# MetaSenseV02_3.net
KiCad netlist of a schematic drawn in EAGLE
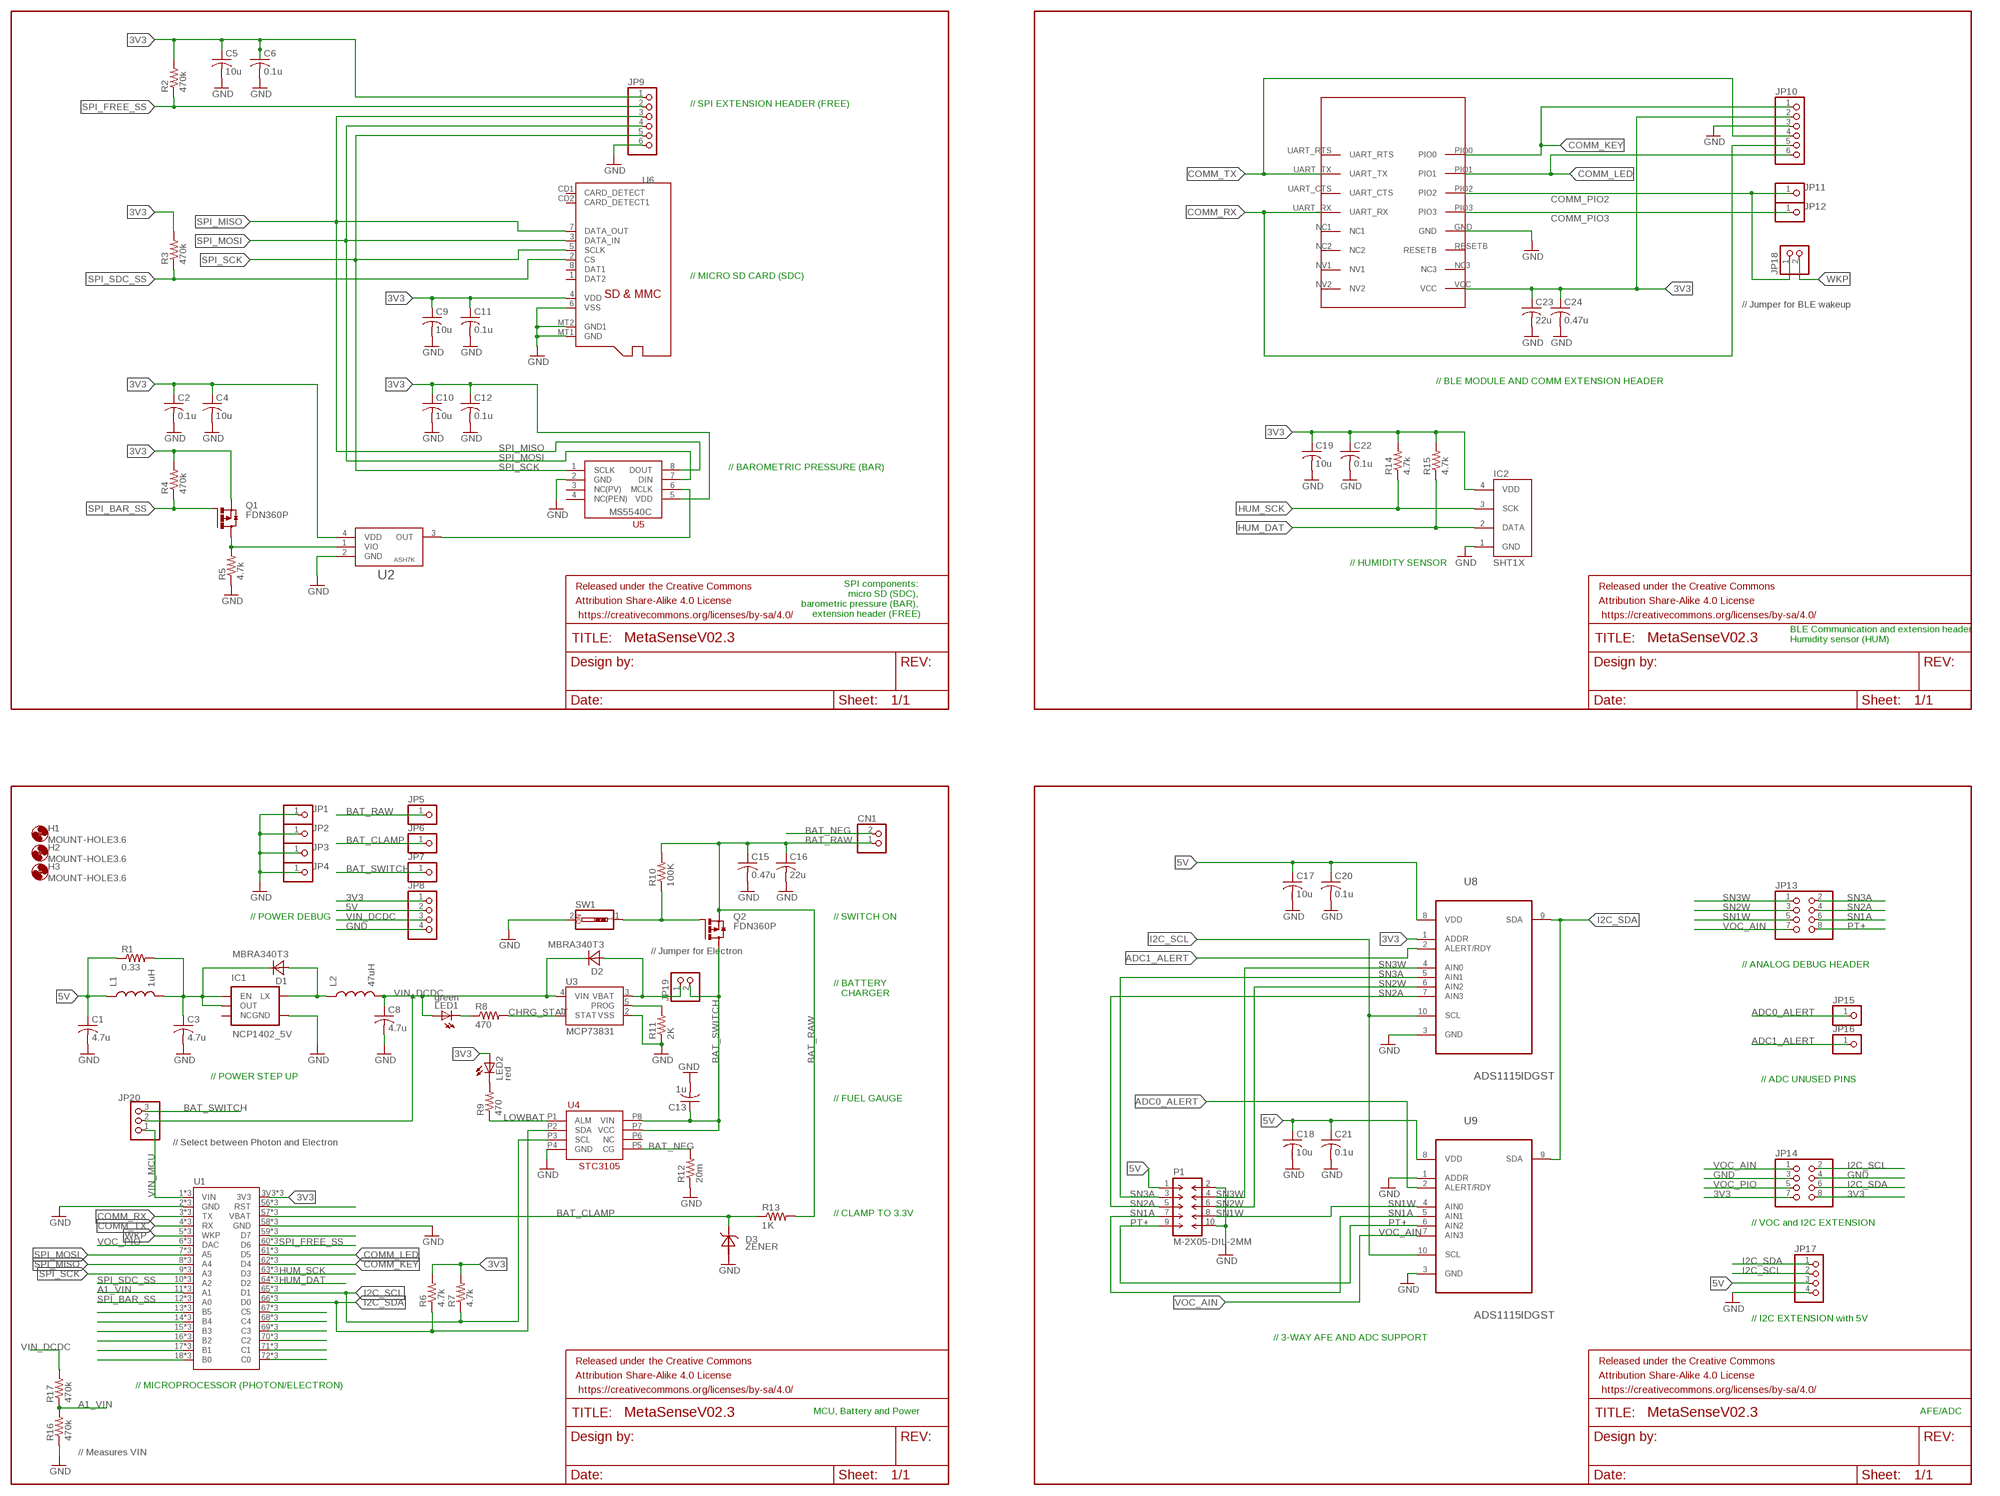
[diagram p0: schematic, sheet 1]

(export (version "E")
  (design (tool "Eeschema 10.0.6"))
  (components
    (comp (ref "C1")
      (value "4.7u")
      (footprint "eagle-import:C0805")
      (fields (field (name "MF") "VISHAY/DALE") (field (name "MPN") "IHLP2525CZER4R7M01"))
      (libsource (lib "eagle-import") (part "C-USC0805"))
    )
    (comp (ref "C2")
      (value "0.1u")
      (footprint "eagle-import:C0805")
      (fields (field (name "MF") "KEMET") (field (name "MPN") "C0603C102J5GACTU"))
      (libsource (lib "eagle-import") (part "C-USC0805"))
    )
    (comp (ref "C3")
      (value "4.7u")
      (footprint "eagle-import:C0805")
      (fields (field (name "MF") "VISHAY/DALE") (field (name "MPN") "IHLP2525CZER4R7M01"))
      (libsource (lib "eagle-import") (part "C-USC0805"))
    )
    (comp (ref "C4")
      (value "10u")
      (footprint "eagle-import:C0805")
      (fields (field (name "MPN") "C0805C106Z8VACTU"))
      (libsource (lib "eagle-import") (part "C-USC0805"))
    )
    (comp (ref "C5")
      (value "10u")
      (footprint "eagle-import:C0805")
      (fields (field (name "MPN") "C0805C106Z8VACTU"))
      (libsource (lib "eagle-import") (part "C-USC0805"))
    )
    (comp (ref "C6")
      (value "0.1u")
      (footprint "eagle-import:C0805")
      (fields (field (name "MF") "KEMET") (field (name "MPN") "C0603C102J5GACTU"))
      (libsource (lib "eagle-import") (part "C-USC0805"))
    )
    (comp (ref "C8")
      (value "4.7u")
      (footprint "eagle-import:C0805")
      (fields (field (name "MF") "VISHAY/DALE") (field (name "MPN") "IHLP2525CZER4R7M01"))
      (libsource (lib "eagle-import") (part "C-USC0805"))
    )
    (comp (ref "C9")
      (value "10u")
      (footprint "eagle-import:C0805")
      (fields (field (name "MPN") "C0805C106Z8VACTU"))
      (libsource (lib "eagle-import") (part "C-USC0805"))
    )
    (comp (ref "C10")
      (value "10u")
      (footprint "eagle-import:C0805")
      (fields (field (name "MPN") "C0805C106Z8VACTU"))
      (libsource (lib "eagle-import") (part "C-USC0805"))
    )
    (comp (ref "C11")
      (value "0.1u")
      (footprint "eagle-import:C0805")
      (fields (field (name "MF") "KEMET") (field (name "MPN") "C0603C102J5GACTU"))
      (libsource (lib "eagle-import") (part "C-USC0805"))
    )
    (comp (ref "C12")
      (value "0.1u")
      (footprint "eagle-import:C0805")
      (fields (field (name "MF") "KEMET") (field (name "MPN") "C0603C102J5GACTU"))
      (libsource (lib "eagle-import") (part "C-USC0805"))
    )
    (comp (ref "C13")
      (value "1u")
      (footprint "eagle-import:C0805")
      (fields (field (name "MF") "KEMET") (field (name "MPN") "C0402C471K5RACTU"))
      (libsource (lib "eagle-import") (part "C-USC0805"))
    )
    (comp (ref "C15")
      (value "0.47u")
      (footprint "eagle-import:C0805")
      (fields (field (name "MF") "KEMET") (field (name "MPN") "C0402C471K5RACTU"))
      (libsource (lib "eagle-import") (part "C-USC0805"))
    )
    (comp (ref "C16")
      (value "22u")
      (footprint "eagle-import:C0805")
      (libsource (lib "eagle-import") (part "C-USC0805"))
    )
    (comp (ref "C17")
      (value "10u")
      (footprint "eagle-import:C0805")
      (fields (field (name "MPN") "C0805C106Z8VACTU"))
      (libsource (lib "eagle-import") (part "C-USC0805"))
    )
    (comp (ref "C18")
      (value "10u")
      (footprint "eagle-import:C0805")
      (fields (field (name "MPN") "C0805C106Z8VACTU"))
      (libsource (lib "eagle-import") (part "C-USC0805"))
    )
    (comp (ref "C19")
      (value "10u")
      (footprint "eagle-import:C0805")
      (fields (field (name "MPN") "C0805C106Z8VACTU"))
      (libsource (lib "eagle-import") (part "C-USC0805"))
    )
    (comp (ref "C20")
      (value "0.1u")
      (footprint "eagle-import:C0805")
      (fields (field (name "MF") "KEMET") (field (name "MPN") "C0603C102J5GACTU"))
      (libsource (lib "eagle-import") (part "C-USC0805"))
    )
    (comp (ref "C21")
      (value "0.1u")
      (footprint "eagle-import:C0805")
      (fields (field (name "MF") "KEMET") (field (name "MPN") "C0603C102J5GACTU"))
      (libsource (lib "eagle-import") (part "C-USC0805"))
    )
    (comp (ref "C22")
      (value "0.1u")
      (footprint "eagle-import:C0805")
      (fields (field (name "MF") "KEMET") (field (name "MPN") "C0603C102J5GACTU"))
      (libsource (lib "eagle-import") (part "C-USC0805"))
    )
    (comp (ref "C23")
      (value "22u")
      (footprint "eagle-import:C0805")
      (libsource (lib "eagle-import") (part "C-USC0805"))
    )
    (comp (ref "C24")
      (value "0.47u")
      (footprint "eagle-import:C0805")
      (fields (field (name "MF") "KEMET") (field (name "MPN") "C0402C471K5RACTU"))
      (libsource (lib "eagle-import") (part "C-USC0805"))
    )
    (comp (ref "CN1")
      (value "JST_2PIN-THM")
      (footprint "eagle-import:JST-PH-2-THM")
      (libsource (lib "eagle-import") (part "JST_2PIN-THM"))
    )
    (comp (ref "D1")
      (value "MBRA340T3")
      (footprint "eagle-import:SMA")
      (libsource (lib "eagle-import") (part "MBRA340T3"))
    )
    (comp (ref "D2")
      (value "MBRA340T3")
      (footprint "eagle-import:SMA")
      (libsource (lib "eagle-import") (part "MBRA340T3"))
    )
    (comp (ref "D3")
      (value "ZENER")
      (footprint "eagle-import:SOD-123_MINI-SMA")
      (libsource (lib "eagle-import") (part "ZENER"))
    )
    (comp (ref "FRAME1")
      (value "FRAME-LETTERNO_PACKAGE")
      (footprint "eagle-import:DUMMY")
      (fields
        (field (name "DESIGNER") "Christine Chan")
        (field (name "VERSION") "v02")
        (field (name "OC_NEWARK") "unknown")
      )
      (libsource (lib "eagle-import") (part "FRAME-LETTERNO_PACKAGE"))
    )
    (comp (ref "FRAME2")
      (value "FRAME-LETTERNO_PACKAGE")
      (footprint "eagle-import:DUMMY")
      (fields
        (field (name "DESIGNER") "Christine Chan")
        (field (name "OC_NEWARK") "unknown")
        (field (name "VERSION") "v02")
      )
      (libsource (lib "eagle-import") (part "FRAME-LETTERNO_PACKAGE"))
    )
    (comp (ref "FRAME3")
      (value "FRAME-LETTERNO_PACKAGE")
      (footprint "eagle-import:DUMMY")
      (fields
        (field (name "DESIGNER") "Christine Chan")
        (field (name "OC_NEWARK") "unknown")
        (field (name "VERSION") "v02")
      )
      (libsource (lib "eagle-import") (part "FRAME-LETTERNO_PACKAGE"))
    )
    (comp (ref "FRAME4")
      (value "FRAME-LETTERNO_PACKAGE")
      (footprint "eagle-import:DUMMY")
      (fields
        (field (name "DESIGNER") "Christine Chan")
        (field (name "VERSION") "v02")
        (field (name "OC_NEWARK") "unknown")
      )
      (libsource (lib "eagle-import") (part "FRAME-LETTERNO_PACKAGE"))
    )
    (comp (ref "H1")
      (value "MOUNT-HOLE3.6")
      (footprint "eagle-import:3,6")
      (libsource (lib "eagle-import") (part "MOUNT-HOLE3.6"))
    )
    (comp (ref "H2")
      (value "MOUNT-HOLE3.6")
      (footprint "eagle-import:3,6")
      (libsource (lib "eagle-import") (part "MOUNT-HOLE3.6"))
    )
    (comp (ref "H3")
      (value "MOUNT-HOLE3.6")
      (footprint "eagle-import:3,6")
      (libsource (lib "eagle-import") (part "MOUNT-HOLE3.6"))
    )
    (comp (ref "IC1")
      (value "NCP1402_5V")
      (footprint "eagle-import:SOT23-5")
      (fields (field (name "MF") "ON SEMICONDUCTOR") (field (name "MPN") "NCP1402SN50T1G"))
      (libsource (lib "eagle-import") (part "V_REG_NCP1400_5V"))
    )
    (comp (ref "IC2")
      (value "SHT1X")
      (footprint "eagle-import:SHT1X")
      (fields (field (name "MF") "SENSIRION AG") (field (name "MPN") "SHT11"))
      (libsource (lib "eagle-import") (part "SHT1X"))
    )
    (comp (ref "JP1")
      (value "PINHD-1X1")
      (footprint "eagle-import:1X01")
      (libsource (lib "eagle-import") (part "pinhead_PINHD-1X1"))
    )
    (comp (ref "JP2")
      (value "PINHD-1X1")
      (footprint "eagle-import:1X01")
      (libsource (lib "eagle-import") (part "pinhead_PINHD-1X1"))
    )
    (comp (ref "JP3")
      (value "PINHD-1X1")
      (footprint "eagle-import:1X01")
      (libsource (lib "eagle-import") (part "pinhead_PINHD-1X1"))
    )
    (comp (ref "JP4")
      (value "PINHD-1X1")
      (footprint "eagle-import:1X01")
      (libsource (lib "eagle-import") (part "pinhead_PINHD-1X1"))
    )
    (comp (ref "JP5")
      (value "PINHD-1X1")
      (footprint "eagle-import:1X01")
      (libsource (lib "eagle-import") (part "pinhead_PINHD-1X1"))
    )
    (comp (ref "JP6")
      (value "PINHD-1X1")
      (footprint "eagle-import:1X01")
      (libsource (lib "eagle-import") (part "pinhead_PINHD-1X1"))
    )
    (comp (ref "JP7")
      (value "PINHD-1X1")
      (footprint "eagle-import:1X01")
      (libsource (lib "eagle-import") (part "pinhead_PINHD-1X1"))
    )
    (comp (ref "JP8")
      (value "PINHD-1X4")
      (footprint "eagle-import:1X04")
      (libsource (lib "eagle-import") (part "PINHD-1X4"))
    )
    (comp (ref "JP9")
      (value "PINHD-1X6")
      (footprint "eagle-import:1X06")
      (libsource (lib "eagle-import") (part "PINHD-1X6"))
    )
    (comp (ref "JP10")
      (value "PINHD-1X6")
      (footprint "eagle-import:1X06")
      (libsource (lib "eagle-import") (part "PINHD-1X6"))
    )
    (comp (ref "JP11")
      (value "PINHD-1X1")
      (footprint "eagle-import:1X01")
      (libsource (lib "eagle-import") (part "pinhead_PINHD-1X1"))
    )
    (comp (ref "JP12")
      (value "PINHD-1X1")
      (footprint "eagle-import:1X01")
      (libsource (lib "eagle-import") (part "pinhead_PINHD-1X1"))
    )
    (comp (ref "JP13")
      (value "PINHD-2X4")
      (footprint "eagle-import:2X04")
      (libsource (lib "eagle-import") (part "PINHD-2X4"))
    )
    (comp (ref "JP14")
      (value "PINHD-2X4")
      (footprint "eagle-import:2X04")
      (libsource (lib "eagle-import") (part "PINHD-2X4"))
    )
    (comp (ref "JP15")
      (value "PINHD-1X1")
      (footprint "eagle-import:1X01")
      (libsource (lib "eagle-import") (part "PINHD-1X1"))
    )
    (comp (ref "JP16")
      (value "PINHD-1X1")
      (footprint "eagle-import:1X01")
      (libsource (lib "eagle-import") (part "PINHD-1X1"))
    )
    (comp (ref "JP17")
      (value "PINHD-1X4")
      (footprint "eagle-import:1X04")
      (libsource (lib "eagle-import") (part "PINHD-1X4"))
    )
    (comp (ref "JP18")
      (value "PINHD-1X2")
      (footprint "eagle-import:1X02")
      (libsource (lib "eagle-import") (part "PINHD-1X2"))
    )
    (comp (ref "JP19")
      (value "PINHD-1X2")
      (footprint "eagle-import:1X02")
      (libsource (lib "eagle-import") (part "PINHD-1X2"))
    )
    (comp (ref "JP20")
      (value "PINHD-1X3")
      (footprint "eagle-import:1X03")
      (libsource (lib "eagle-import") (part "PINHD-1X3"))
    )
    (comp (ref "L1")
      (value "1uH")
      (footprint "eagle-import:0805")
      (fields (field (name "MPN") "LQM21NN1R0K10D"))
      (libsource (lib "eagle-import") (part "INDUCTOR0805"))
    )
    (comp (ref "L2")
      (value "47uH")
      (footprint "eagle-import:0805")
      (libsource (lib "eagle-import") (part "INDUCTOR0805"))
    )
    (comp (ref "LED1")
      (value "green")
      (footprint "eagle-import:CHIPLED_0805")
      (fields (field (name "MPN") "NTE30003"))
      (libsource (lib "eagle-import") (part "LEDCHIPLED_0805"))
    )
    (comp (ref "LED2")
      (value "red")
      (footprint "eagle-import:CHIPLED_0805")
      (fields (field (name "MPN") "NTE30002"))
      (libsource (lib "eagle-import") (part "LEDCHIPLED_0805"))
    )
    (comp (ref "P1")
      (value "M-2X05-DIL-2MM")
      (footprint "eagle-import:DIL-2MM-2X05")
      (libsource (lib "eagle-import") (part "M-2X05-DIL-2MM"))
    )
    (comp (ref "Q1")
      (value "FDN360P")
      (footprint "eagle-import:SUPER-SOT3")
      (fields (field (name "MF") "FAIRCHILD SEMICONDUCTOR"))
      (libsource (lib "eagle-import") (part "FDN360P"))
    )
    (comp (ref "Q2")
      (value "FDN360P")
      (footprint "eagle-import:SUPER-SOT3")
      (fields (field (name "MF") "FAIRCHILD SEMICONDUCTOR"))
      (libsource (lib "eagle-import") (part "FDN360P"))
    )
    (comp (ref "R1")
      (value "0.33")
      (footprint "eagle-import:R0805")
      (libsource (lib "eagle-import") (part "R-US_R0805"))
    )
    (comp (ref "R2")
      (value "470k")
      (footprint "eagle-import:R0805")
      (fields (field (name "MF") "VISHAY/DALE") (field (name "MPN") "CRCW0805470KJNEA"))
      (libsource (lib "eagle-import") (part "R-US_R0805"))
    )
    (comp (ref "R3")
      (value "470k")
      (footprint "eagle-import:R0805")
      (fields (field (name "MF") "VISHAY/DALE") (field (name "MPN") "CRCW0805470KJNEA"))
      (libsource (lib "eagle-import") (part "R-US_R0805"))
    )
    (comp (ref "R4")
      (value "470k")
      (footprint "eagle-import:R0805")
      (fields (field (name "MF") "VISHAY/DALE") (field (name "MPN") "CRCW0805470KJNEA"))
      (libsource (lib "eagle-import") (part "R-US_R0805"))
    )
    (comp (ref "R5")
      (value "4.7k")
      (footprint "eagle-import:R0805")
      (fields (field (name "MF") "VISHAY/DALE") (field (name "MPN") "CRCW08054K70JNEA"))
      (libsource (lib "eagle-import") (part "R-US_R0805"))
    )
    (comp (ref "R6")
      (value "4.7k")
      (footprint "eagle-import:R0805")
      (fields (field (name "MF") "VISHAY/DALE") (field (name "MPN") "CRCW08054K70JNEA"))
      (libsource (lib "eagle-import") (part "R-US_R0805"))
    )
    (comp (ref "R7")
      (value "4.7k")
      (footprint "eagle-import:R0805")
      (fields (field (name "MF") "VISHAY/DALE") (field (name "MPN") "CRCW08054K70JNEA"))
      (libsource (lib "eagle-import") (part "R-US_R0805"))
    )
    (comp (ref "R8")
      (value "470")
      (footprint "eagle-import:R0805")
      (libsource (lib "eagle-import") (part "R-US_R0805"))
    )
    (comp (ref "R9")
      (value "470")
      (footprint "eagle-import:R0805")
      (libsource (lib "eagle-import") (part "R-US_R0805"))
    )
    (comp (ref "R10")
      (value "100K")
      (footprint "eagle-import:R0805")
      (fields (field (name "MPN") "ERA-6AEB104V"))
      (libsource (lib "eagle-import") (part "R-US_R0805"))
    )
    (comp (ref "R11")
      (value "2K")
      (footprint "eagle-import:R0805")
      (libsource (lib "eagle-import") (part "R-US_R0805"))
    )
    (comp (ref "R12")
      (value "20m")
      (footprint "eagle-import:R0805")
      (libsource (lib "eagle-import") (part "R-US_R0805"))
    )
    (comp (ref "R13")
      (value "1K")
      (footprint "eagle-import:R0805")
      (fields (field (name "MPN") "ERJ-6ENF1001V"))
      (libsource (lib "eagle-import") (part "R-US_R0805"))
    )
    (comp (ref "R14")
      (value "4.7k")
      (footprint "eagle-import:R0805")
      (fields (field (name "MF") "VISHAY/DALE") (field (name "MPN") "CRCW08054K70JNEA"))
      (libsource (lib "eagle-import") (part "R-US_R0805"))
    )
    (comp (ref "R15")
      (value "4.7k")
      (footprint "eagle-import:R0805")
      (fields (field (name "MF") "VISHAY/DALE") (field (name "MPN") "CRCW08054K70JNEA"))
      (libsource (lib "eagle-import") (part "R-US_R0805"))
    )
    (comp (ref "R16")
      (value "470k")
      (footprint "eagle-import:R0805")
      (fields (field (name "MF") "VISHAY/DALE") (field (name "MPN") "CRCW08054K70JNEA"))
      (libsource (lib "eagle-import") (part "R-US_R0805"))
    )
    (comp (ref "R17")
      (value "470k")
      (footprint "eagle-import:R0805")
      (fields (field (name "MF") "VISHAY/DALE") (field (name "MPN") "CRCW08054K70JNEA"))
      (libsource (lib "eagle-import") (part "R-US_R0805"))
    )
    (comp (ref "SW1")
      (value "SW_DIP-1")
      (footprint "eagle-import:EDG-01")
      (libsource (lib "eagle-import") (part "SW_DIP-1"))
    )
    (comp (ref "U1")
      (value "ELECTRONDUALROW")
      (footprint "eagle-import:ELECTRON_DUAL-ROW")
      (libsource (lib "eagle-import") (part "ELECTRONDUALROW"))
    )
    (comp (ref "U2")
      (value "ASH7K-OSCILLATOR")
      (footprint "eagle-import:SMD-4PAD")
      (libsource (lib "eagle-import") (part "ASH7K-OSCILLATOR"))
    )
    (comp (ref "U3")
      (value "MCP73831")
      (footprint "eagle-import:SOT23-5")
      (fields (field (name "MPN") "MCP73831T-2DCI/OT"))
      (libsource (lib "eagle-import") (part "MCP73831"))
    )
    (comp (ref "U4")
      (value "STC3105")
      (footprint "eagle-import:TDFN-8-3X2MM")
      (libsource (lib "eagle-import") (part "STC3105"))
    )
    (comp (ref "U5")
      (value "MS5540CSMD")
      (footprint "eagle-import:SMD-HYBRID")
      (libsource (lib "eagle-import") (part "MS5540CSMD"))
    )
    (comp (ref "U6")
      (value "MICROSD")
      (footprint "eagle-import:MICROSD")
      (fields (field (name "MPN") "2908-05WB-MG"))
      (libsource (lib "eagle-import") (part "MICROSD"))
    )
    (comp (ref "U7")
      (value "HM-11")
      (footprint "eagle-import:HM-11")
      (libsource (lib "eagle-import") (part "HM-11"))
    )
    (comp (ref "U8")
      (value "ADS1115IDGST")
      (footprint "eagle-import:SOP50P490X110-10N")
      (libsource (lib "eagle-import") (part "ADS1115IDGST"))
    )
    (comp (ref "U9")
      (value "ADS1115IDGST")
      (footprint "eagle-import:SOP50P490X110-10N")
      (libsource (lib "eagle-import") (part "ADS1115IDGST"))
    )
  )
  (nets
    (net (code "1") (name "/A1_VIN") (class "Default")
      (node (ref "R16") (pin "2") (pinfunction "2_2") (pintype "passive"))
      (node (ref "R17") (pin "1") (pinfunction "1_1") (pintype "passive"))
      (node (ref "U1") (pin "11") (pinfunction "A1_11") (pintype "bidirectional"))
      (node (ref "U1") (pin "47") (pinfunction "A1_47") (pintype "bidirectional"))
      (node (ref "U1") (pin "A1") (pinfunction "A1_A1") (pintype "bidirectional"))
    )
    (net (code "2") (name "/BAT_CLAMP") (class "Default")
      (node (ref "D3") (pin "C") (pinfunction "CAT_C") (pintype "bidirectional"))
      (node (ref "JP6") (pin "1") (pinfunction "1_1") (pintype "passive"))
      (node (ref "R13") (pin "1") (pinfunction "1_1") (pintype "passive"))
      (node (ref "U1") (pin "57") (pinfunction "VBAT_57") (pintype "passive"))
      (node (ref "U1") (pin "93") (pinfunction "VBAT_93") (pintype "passive"))
      (node (ref "U1") (pin "VBAT") (pinfunction "VBAT_VBAT") (pintype "passive"))
    )
    (net (code "3") (name "/BAT_NEG") (class "Default")
      (node (ref "CN1") (pin "2") (pinfunction "1_2") (pintype "passive"))
      (node (ref "R12") (pin "2") (pinfunction "2_2") (pintype "passive"))
      (node (ref "U4") (pin "P5") (pinfunction "CG_P5") (pintype "bidirectional"))
    )
    (net (code "4") (name "/BAT_RAW") (class "Default")
      (node (ref "C15") (pin "1") (pinfunction "1_1") (pintype "passive"))
      (node (ref "C16") (pin "1") (pinfunction "1_1") (pintype "passive"))
      (node (ref "CN1") (pin "1") (pinfunction "2_1") (pintype "passive"))
      (node (ref "JP5") (pin "1") (pinfunction "1_1") (pintype "passive"))
      (node (ref "Q2") (pin "2") (pinfunction "S_2") (pintype "passive"))
      (node (ref "R10") (pin "2") (pinfunction "2_2") (pintype "passive"))
      (node (ref "R13") (pin "2") (pinfunction "2_2") (pintype "passive"))
    )
    (net (code "5") (name "/BAT_SWITCH") (class "Default")
      (node (ref "C13") (pin "1") (pinfunction "1_1") (pintype "passive"))
      (node (ref "JP19") (pin "2") (pinfunction "2_2") (pintype "passive"))
      (node (ref "JP20") (pin "3") (pinfunction "3_3") (pintype "passive"))
      (node (ref "JP7") (pin "1") (pinfunction "1_1") (pintype "passive"))
      (node (ref "Q2") (pin "3") (pinfunction "D_3") (pintype "passive"))
      (node (ref "U4") (pin "P7") (pinfunction "VCC_P7") (pintype "bidirectional"))
      (node (ref "U4") (pin "P8") (pinfunction "VIN_P8") (pintype "bidirectional"))
    )
    (net (code "6") (name "/CHRG_STAT") (class "Default")
      (node (ref "R8") (pin "2") (pinfunction "2_2") (pintype "passive"))
      (node (ref "U3") (pin "1") (pinfunction "STAT_1") (pintype "output"))
    )
    (net (code "7") (name "/COMM_PIO2") (class "Default")
      (node (ref "JP11") (pin "1") (pinfunction "1_1") (pintype "passive"))
      (node (ref "JP18") (pin "1") (pinfunction "1_1") (pintype "passive"))
      (node (ref "U7") (pin "PIO2") (pinfunction "PIO2_PIO2") (pintype "bidirectional"))
    )
    (net (code "8") (name "/COMM_PIO3") (class "Default")
      (node (ref "JP12") (pin "1") (pinfunction "1_1") (pintype "passive"))
      (node (ref "U7") (pin "PIO3") (pinfunction "PIO3_PIO3") (pintype "bidirectional"))
    )
    (net (code "9") (name "/LOWBAT") (class "Default")
      (node (ref "R9") (pin "1") (pinfunction "1_1") (pintype "passive"))
      (node (ref "U4") (pin "P1") (pinfunction "ALM_P1") (pintype "bidirectional"))
    )
    (net (code "10") (name "/PT+") (class "Default")
      (node (ref "JP13") (pin "8") (pinfunction "8_8") (pintype "passive"))
      (node (ref "P1") (pin "9") (pinfunction "9_9") (pintype "passive"))
      (node (ref "U9") (pin "6") (pinfunction "AIN2_6") (pintype "input"))
    )
    (net (code "11") (name "/SN1A") (class "Default")
      (node (ref "JP13") (pin "6") (pinfunction "6_6") (pintype "passive"))
      (node (ref "P1") (pin "7") (pinfunction "7_7") (pintype "passive"))
      (node (ref "U9") (pin "5") (pinfunction "AIN1_5") (pintype "input"))
    )
    (net (code "12") (name "/SN1W") (class "Default")
      (node (ref "JP13") (pin "5") (pinfunction "5_5") (pintype "passive"))
      (node (ref "P1") (pin "8") (pinfunction "8_8") (pintype "passive"))
      (node (ref "U9") (pin "4") (pinfunction "AIN0_4") (pintype "input"))
    )
    (net (code "13") (name "/SN2A") (class "Default")
      (node (ref "JP13") (pin "4") (pinfunction "4_4") (pintype "passive"))
      (node (ref "P1") (pin "5") (pinfunction "5_5") (pintype "passive"))
      (node (ref "U8") (pin "7") (pinfunction "AIN3_7") (pintype "input"))
    )
    (net (code "14") (name "/SN2W") (class "Default")
      (node (ref "JP13") (pin "3") (pinfunction "3_3") (pintype "passive"))
      (node (ref "P1") (pin "6") (pinfunction "6_6") (pintype "passive"))
      (node (ref "U8") (pin "6") (pinfunction "AIN2_6") (pintype "input"))
    )
    (net (code "15") (name "/SN3A") (class "Default")
      (node (ref "JP13") (pin "2") (pinfunction "2_2") (pintype "passive"))
      (node (ref "P1") (pin "3") (pinfunction "3_3") (pintype "passive"))
      (node (ref "U8") (pin "5") (pinfunction "AIN1_5") (pintype "input"))
    )
    (net (code "16") (name "/SN3W") (class "Default")
      (node (ref "JP13") (pin "1") (pinfunction "1_1") (pintype "passive"))
      (node (ref "P1") (pin "4") (pinfunction "4_4") (pintype "passive"))
      (node (ref "U8") (pin "4") (pinfunction "AIN0_4") (pintype "input"))
    )
    (net (code "17") (name "/VIN_DCDC") (class "Default")
      (node (ref "C8") (pin "1") (pinfunction "1_1") (pintype "passive"))
      (node (ref "D2") (pin "C") (pinfunction "C_C") (pintype "passive"))
      (node (ref "JP20") (pin "2") (pinfunction "2_2") (pintype "passive"))
      (node (ref "JP8") (pin "3") (pinfunction "3_3") (pintype "passive"))
      (node (ref "L2") (pin "2") (pinfunction "2_2") (pintype "passive"))
      (node (ref "LED1") (pin "A") (pinfunction "A_A") (pintype "passive"))
      (node (ref "R17") (pin "2") (pinfunction "2_2") (pintype "passive"))
      (node (ref "U3") (pin "4") (pinfunction "VIN_4") (pintype "power_in"))
    )
    (net (code "18") (name "/VIN_MCU") (class "Default")
      (node (ref "JP20") (pin "1") (pinfunction "1_1") (pintype "passive"))
      (node (ref "U1") (pin "1") (pinfunction "VIN_1") (pintype "power_in"))
      (node (ref "U1") (pin "37") (pinfunction "VIN_37") (pintype "power_in"))
      (node (ref "U1") (pin "VIN") (pinfunction "VIN_VIN") (pintype "power_in"))
    )
    (net (code "19") (name "/VOC_PIO") (class "Default")
      (node (ref "JP14") (pin "5") (pinfunction "5_5") (pintype "passive"))
      (node (ref "U1") (pin "42") (pinfunction "DAC_42") (pintype "bidirectional"))
      (node (ref "U1") (pin "6") (pinfunction "DAC_6") (pintype "bidirectional"))
      (node (ref "U1") (pin "DAC") (pinfunction "DAC_DAC") (pintype "bidirectional"))
    )
    (net (code "20") (name "3V3") (class "Default")
      (node (ref "C10") (pin "1") (pinfunction "1_1") (pintype "passive"))
      (node (ref "C11") (pin "1") (pinfunction "1_1") (pintype "passive"))
      (node (ref "C12") (pin "1") (pinfunction "1_1") (pintype "passive"))
      (node (ref "C19") (pin "1") (pinfunction "1_1") (pintype "passive"))
      (node (ref "C2") (pin "1") (pinfunction "1_1") (pintype "passive"))
      (node (ref "C22") (pin "1") (pinfunction "1_1") (pintype "passive"))
      (node (ref "C23") (pin "1") (pinfunction "1_1") (pintype "passive"))
      (node (ref "C24") (pin "1") (pinfunction "1_1") (pintype "passive"))
      (node (ref "C4") (pin "1") (pinfunction "1_1") (pintype "passive"))
      (node (ref "C5") (pin "1") (pinfunction "1_1") (pintype "passive"))
      (node (ref "C6") (pin "1") (pinfunction "1_1") (pintype "passive"))
      (node (ref "C9") (pin "1") (pinfunction "1_1") (pintype "passive"))
      (node (ref "IC2") (pin "4") (pinfunction "VDD_4") (pintype "power_in"))
      (node (ref "JP10") (pin "2") (pinfunction "2_2") (pintype "passive"))
      (node (ref "JP14") (pin "7") (pinfunction "7_7") (pintype "passive"))
      (node (ref "JP14") (pin "8") (pinfunction "8_8") (pintype "passive"))
      (node (ref "JP8") (pin "1") (pinfunction "1_1") (pintype "passive"))
      (node (ref "JP9") (pin "1") (pinfunction "1_1") (pintype "passive"))
      (node (ref "LED2") (pin "A") (pinfunction "A_A") (pintype "passive"))
      (node (ref "Q1") (pin "2") (pinfunction "S_2") (pintype "passive"))
      (node (ref "R14") (pin "2") (pinfunction "2_2") (pintype "passive"))
      (node (ref "R15") (pin "2") (pinfunction "2_2") (pintype "passive"))
      (node (ref "R2") (pin "2") (pinfunction "2_2") (pintype "passive"))
      (node (ref "R3") (pin "2") (pinfunction "2_2") (pintype "passive"))
      (node (ref "R4") (pin "2") (pinfunction "2_2") (pintype "passive"))
      (node (ref "R6") (pin "2") (pinfunction "2_2") (pintype "passive"))
      (node (ref "R7") (pin "2") (pinfunction "2_2") (pintype "passive"))
      (node (ref "U1") (pin "3V3") (pinfunction "3V3_3V3") (pintype "power_in"))
      (node (ref "U1") (pin "55") (pinfunction "3V3_55") (pintype "power_in"))
      (node (ref "U1") (pin "91") (pinfunction "3V3_91") (pintype "power_in"))
      (node (ref "U2") (pin "4") (pinfunction "VDD_4") (pintype "bidirectional"))
      (node (ref "U5") (pin "5") (pinfunction "VDD_5") (pintype "bidirectional"))
      (node (ref "U6") (pin "4") (pinfunction "VDD_4") (pintype "power_in"))
      (node (ref "U7") (pin "VCC") (pinfunction "VCC_VCC") (pintype "bidirectional"))
      (node (ref "U8") (pin "1") (pinfunction "ADDR_1") (pintype "input"))
    )
    (net (code "21") (name "5V") (class "Default")
      (node (ref "C1") (pin "1") (pinfunction "1_1") (pintype "passive"))
      (node (ref "C17") (pin "1") (pinfunction "1_1") (pintype "passive"))
      (node (ref "C18") (pin "1") (pinfunction "1_1") (pintype "passive"))
      (node (ref "C20") (pin "1") (pinfunction "1_1") (pintype "passive"))
      (node (ref "C21") (pin "1") (pinfunction "1_1") (pintype "passive"))
      (node (ref "JP17") (pin "3") (pinfunction "3_3") (pintype "passive"))
      (node (ref "JP8") (pin "2") (pinfunction "2_2") (pintype "passive"))
      (node (ref "L1") (pin "1") (pinfunction "1_1") (pintype "passive"))
      (node (ref "P1") (pin "1") (pinfunction "1_1") (pintype "passive"))
      (node (ref "R1") (pin "1") (pinfunction "1_1") (pintype "passive"))
      (node (ref "U8") (pin "8") (pinfunction "VDD_8") (pintype "power_in"))
      (node (ref "U9") (pin "8") (pinfunction "VDD_8") (pintype "power_in"))
    )
    (net (code "22") (name "ADC0_ALERT") (class "Default")
      (node (ref "JP15") (pin "1") (pinfunction "1_1") (pintype "passive"))
      (node (ref "U9") (pin "2") (pinfunction "ALERT/RDY_2") (pintype "input"))
    )
    (net (code "23") (name "ADC1_ALERT") (class "Default")
      (node (ref "JP16") (pin "1") (pinfunction "1_1") (pintype "passive"))
      (node (ref "U8") (pin "2") (pinfunction "ALERT/RDY_2") (pintype "input"))
    )
    (net (code "24") (name "COMM_KEY") (class "Default")
      (node (ref "JP10") (pin "1") (pinfunction "1_1") (pintype "passive"))
      (node (ref "U1") (pin "62") (pinfunction "D4_62") (pintype "bidirectional"))
      (node (ref "U1") (pin "98") (pinfunction "D4_98") (pintype "bidirectional"))
      (node (ref "U1") (pin "D4") (pinfunction "D4_D4") (pintype "bidirectional"))
      (node (ref "U7") (pin "PIO0") (pinfunction "PIO0_PIO0") (pintype "bidirectional"))
    )
    (net (code "25") (name "COMM_LED") (class "Default")
      (node (ref "JP10") (pin "6") (pinfunction "6_6") (pintype "passive"))
      (node (ref "U1") (pin "61") (pinfunction "D5_61") (pintype "bidirectional"))
      (node (ref "U1") (pin "97") (pinfunction "D5_97") (pintype "bidirectional"))
      (node (ref "U1") (pin "D5") (pinfunction "D5_D5") (pintype "bidirectional"))
      (node (ref "U7") (pin "PIO1") (pinfunction "PIO1_PIO1") (pintype "bidirectional"))
    )
    (net (code "26") (name "COMM_RX") (class "Default")
      (node (ref "JP10") (pin "5") (pinfunction "5_5") (pintype "passive"))
      (node (ref "U1") (pin "3") (pinfunction "TX_3") (pintype "bidirectional"))
      (node (ref "U1") (pin "39") (pinfunction "TX_39") (pintype "bidirectional"))
      (node (ref "U1") (pin "TX") (pinfunction "TX_TX") (pintype "bidirectional"))
      (node (ref "U7") (pin "UART_RX") (pinfunction "UART_RX_UART_RX") (pintype "bidirectional"))
    )
    (net (code "27") (name "COMM_TX") (class "Default")
      (node (ref "JP10") (pin "4") (pinfunction "4_4") (pintype "passive"))
      (node (ref "U1") (pin "4") (pinfunction "RX_4") (pintype "bidirectional"))
      (node (ref "U1") (pin "40") (pinfunction "RX_40") (pintype "bidirectional"))
      (node (ref "U1") (pin "RX") (pinfunction "RX_RX") (pintype "bidirectional"))
      (node (ref "U7") (pin "UART_TX") (pinfunction "UART_TX_UART_TX") (pintype "bidirectional"))
    )
    (net (code "28") (name "GND") (class "Default")
      (node (ref "C1") (pin "2") (pinfunction "2_2") (pintype "passive"))
      (node (ref "C10") (pin "2") (pinfunction "2_2") (pintype "passive"))
      (node (ref "C11") (pin "2") (pinfunction "2_2") (pintype "passive"))
      (node (ref "C12") (pin "2") (pinfunction "2_2") (pintype "passive"))
      (node (ref "C13") (pin "2") (pinfunction "2_2") (pintype "passive"))
      (node (ref "C15") (pin "2") (pinfunction "2_2") (pintype "passive"))
      (node (ref "C16") (pin "2") (pinfunction "2_2") (pintype "passive"))
      (node (ref "C17") (pin "2") (pinfunction "2_2") (pintype "passive"))
      (node (ref "C18") (pin "2") (pinfunction "2_2") (pintype "passive"))
      (node (ref "C19") (pin "2") (pinfunction "2_2") (pintype "passive"))
      (node (ref "C2") (pin "2") (pinfunction "2_2") (pintype "passive"))
      (node (ref "C20") (pin "2") (pinfunction "2_2") (pintype "passive"))
      (node (ref "C21") (pin "2") (pinfunction "2_2") (pintype "passive"))
      (node (ref "C22") (pin "2") (pinfunction "2_2") (pintype "passive"))
      (node (ref "C23") (pin "2") (pinfunction "2_2") (pintype "passive"))
      (node (ref "C24") (pin "2") (pinfunction "2_2") (pintype "passive"))
      (node (ref "C3") (pin "2") (pinfunction "2_2") (pintype "passive"))
      (node (ref "C4") (pin "2") (pinfunction "2_2") (pintype "passive"))
      (node (ref "C5") (pin "2") (pinfunction "2_2") (pintype "passive"))
      (node (ref "C6") (pin "2") (pinfunction "2_2") (pintype "passive"))
      (node (ref "C8") (pin "2") (pinfunction "2_2") (pintype "passive"))
      (node (ref "C9") (pin "2") (pinfunction "2_2") (pintype "passive"))
      (node (ref "D3") (pin "A") (pinfunction "AN_A") (pintype "bidirectional"))
      (node (ref "IC1") (pin "4") (pinfunction "GND_4") (pintype "input"))
      (node (ref "IC2") (pin "1") (pinfunction "GND_1") (pintype "power_in"))
      (node (ref "JP1") (pin "1") (pinfunction "1_1") (pintype "passive"))
      (node (ref "JP10") (pin "3") (pinfunction "3_3") (pintype "passive"))
      (node (ref "JP14") (pin "3") (pinfunction "3_3") (pintype "passive"))
      (node (ref "JP14") (pin "4") (pinfunction "4_4") (pintype "passive"))
      (node (ref "JP17") (pin "4") (pinfunction "4_4") (pintype "passive"))
      (node (ref "JP2") (pin "1") (pinfunction "1_1") (pintype "passive"))
      (node (ref "JP3") (pin "1") (pinfunction "1_1") (pintype "passive"))
      (node (ref "JP4") (pin "1") (pinfunction "1_1") (pintype "passive"))
      (node (ref "JP8") (pin "4") (pinfunction "4_4") (pintype "passive"))
      (node (ref "JP9") (pin "6") (pinfunction "6_6") (pintype "passive"))
      (node (ref "P1") (pin "10") (pinfunction "10_10") (pintype "passive"))
      (node (ref "P1") (pin "2") (pinfunction "2_2") (pintype "passive"))
      (node (ref "R11") (pin "1") (pinfunction "1_1") (pintype "passive"))
      (node (ref "R12") (pin "1") (pinfunction "1_1") (pintype "passive"))
      (node (ref "R16") (pin "1") (pinfunction "1_1") (pintype "passive"))
      (node (ref "R5") (pin "1") (pinfunction "1_1") (pintype "passive"))
      (node (ref "SW1") (pin "2") (pinfunction "2_2") (pintype "passive"))
      (node (ref "U1") (pin "2") (pinfunction "GND_2") (pintype "power_in"))
      (node (ref "U1") (pin "38") (pinfunction "GND_38") (pintype "power_in"))
      (node (ref "U1") (pin "58") (pinfunction "GND_58") (pintype "power_in"))
      (node (ref "U1") (pin "94") (pinfunction "GND_94") (pintype "power_in"))
      (node (ref "U1") (pin "GND") (pinfunction "GND_GND") (pintype "power_in"))
      (node (ref "U1") (pin "GND@2") (pinfunction "GND_GND@2") (pintype "power_in"))
      (node (ref "U2") (pin "2") (pinfunction "GND_2") (pintype "bidirectional"))
      (node (ref "U3") (pin "2") (pinfunction "VSS_2") (pintype "power_in"))
      (node (ref "U4") (pin "P4") (pinfunction "GND_P4") (pintype "bidirectional"))
      (node (ref "U5") (pin "2") (pinfunction "GND_2") (pintype "bidirectional"))
      (node (ref "U6") (pin "6") (pinfunction "VSS_6") (pintype "power_in"))
      (node (ref "U6") (pin "MT1") (pinfunction "GND_MT1") (pintype "power_in"))
      (node (ref "U6") (pin "MT2") (pinfunction "GND1_MT2") (pintype "power_in"))
      (node (ref "U7") (pin "GND") (pinfunction "GND_GND") (pintype "bidirectional"))
      (node (ref "U8") (pin "3") (pinfunction "GND_3") (pintype "passive"))
      (node (ref "U9") (pin "1") (pinfunction "ADDR_1") (pintype "input"))
      (node (ref "U9") (pin "3") (pinfunction "GND_3") (pintype "passive"))
    )
    (net (code "29") (name "HUM_DAT") (class "Default")
      (node (ref "IC2") (pin "2") (pinfunction "DATA_2") (pintype "open_collector"))
      (node (ref "R15") (pin "1") (pinfunction "1_1") (pintype "passive"))
      (node (ref "U1") (pin "100") (pinfunction "D2_100") (pintype "bidirectional"))
      (node (ref "U1") (pin "64") (pinfunction "D2_64") (pintype "bidirectional"))
      (node (ref "U1") (pin "D2") (pinfunction "D2_D2") (pintype "bidirectional"))
    )
    (net (code "30") (name "HUM_SCK") (class "Default")
      (node (ref "IC2") (pin "3") (pinfunction "SCK_3") (pintype "input"))
      (node (ref "R14") (pin "1") (pinfunction "1_1") (pintype "passive"))
      (node (ref "U1") (pin "63") (pinfunction "D3_63") (pintype "bidirectional"))
      (node (ref "U1") (pin "99") (pinfunction "D3_99") (pintype "bidirectional"))
      (node (ref "U1") (pin "D3") (pinfunction "D3_D3") (pintype "bidirectional"))
    )
    (net (code "31") (name "I2C_SCL") (class "Default")
      (node (ref "JP14") (pin "2") (pinfunction "2_2") (pintype "passive"))
      (node (ref "JP17") (pin "2") (pinfunction "2_2") (pintype "passive"))
      (node (ref "R7") (pin "1") (pinfunction "1_1") (pintype "passive"))
      (node (ref "U1") (pin "101") (pinfunction "D1_101") (pintype "bidirectional"))
      (node (ref "U1") (pin "65") (pinfunction "D1_65") (pintype "bidirectional"))
      (node (ref "U1") (pin "D1") (pinfunction "D1_D1") (pintype "bidirectional"))
      (node (ref "U4") (pin "P3") (pinfunction "SCL_P3") (pintype "bidirectional"))
      (node (ref "U8") (pin "10") (pinfunction "SCL_10") (pintype "input"))
      (node (ref "U9") (pin "10") (pinfunction "SCL_10") (pintype "input"))
    )
    (net (code "32") (name "I2C_SDA") (class "Default")
      (node (ref "JP14") (pin "6") (pinfunction "6_6") (pintype "passive"))
      (node (ref "JP17") (pin "1") (pinfunction "1_1") (pintype "passive"))
      (node (ref "R6") (pin "1") (pinfunction "1_1") (pintype "passive"))
      (node (ref "U1") (pin "102") (pinfunction "D0_102") (pintype "bidirectional"))
      (node (ref "U1") (pin "66") (pinfunction "D0_66") (pintype "bidirectional"))
      (node (ref "U1") (pin "D0") (pinfunction "D0_D0") (pintype "bidirectional"))
      (node (ref "U4") (pin "P2") (pinfunction "SDA_P2") (pintype "bidirectional"))
      (node (ref "U8") (pin "9") (pinfunction "SDA_9") (pintype "bidirectional"))
      (node (ref "U9") (pin "9") (pinfunction "SDA_9") (pintype "bidirectional"))
    )
    (net (code "33") (name "Net-(IC1-EN)") (class "Default")
      (node (ref "C3") (pin "1") (pinfunction "1_1") (pintype "passive"))
      (node (ref "D1") (pin "C") (pinfunction "C_C") (pintype "passive"))
      (node (ref "IC1") (pin "1") (pinfunction "EN_1") (pintype "input"))
      (node (ref "IC1") (pin "2") (pinfunction "OUT_2") (pintype "passive"))
      (node (ref "L1") (pin "2") (pinfunction "2_2") (pintype "passive"))
      (node (ref "R1") (pin "2") (pinfunction "2_2") (pintype "passive"))
    )
    (net (code "34") (name "Net-(IC1-LX)") (class "Default")
      (node (ref "D1") (pin "A") (pinfunction "A_A") (pintype "passive"))
      (node (ref "IC1") (pin "5") (pinfunction "LX_5") (pintype "input"))
      (node (ref "L2") (pin "1") (pinfunction "1_1") (pintype "passive"))
    )
    (net (code "35") (name "Net-(LED1-PadC)") (class "Default")
      (node (ref "LED1") (pin "C") (pinfunction "C_C") (pintype "passive"))
      (node (ref "R8") (pin "1") (pinfunction "1_1") (pintype "passive"))
    )
    (net (code "36") (name "Net-(LED2-PadC)") (class "Default")
      (node (ref "LED2") (pin "C") (pinfunction "C_C") (pintype "passive"))
      (node (ref "R9") (pin "2") (pinfunction "2_2") (pintype "passive"))
    )
    (net (code "37") (name "Net-(Q1-D)") (class "Default")
      (node (ref "Q1") (pin "3") (pinfunction "D_3") (pintype "passive"))
      (node (ref "R5") (pin "2") (pinfunction "2_2") (pintype "passive"))
      (node (ref "U2") (pin "1") (pinfunction "VIO_1") (pintype "bidirectional"))
    )
    (net (code "38") (name "Net-(Q2-G)") (class "Default")
      (node (ref "Q2") (pin "1") (pinfunction "G_1") (pintype "passive"))
      (node (ref "R10") (pin "1") (pinfunction "1_1") (pintype "passive"))
      (node (ref "SW1") (pin "1") (pinfunction "1_1") (pintype "passive"))
    )
    (net (code "39") (name "Net-(U1-B0-Pad18)") (class "Default")
      (node (ref "U1") (pin "18") (pinfunction "B0_18") (pintype "bidirectional"))
      (node (ref "U1") (pin "54") (pinfunction "B0_54") (pintype "bidirectional"))
      (node (ref "U1") (pin "B0") (pinfunction "B0_B0") (pintype "bidirectional"))
    )
    (net (code "40") (name "Net-(U1-B1-Pad17)") (class "Default")
      (node (ref "U1") (pin "17") (pinfunction "B1_17") (pintype "bidirectional"))
      (node (ref "U1") (pin "53") (pinfunction "B1_53") (pintype "bidirectional"))
      (node (ref "U1") (pin "B1") (pinfunction "B1_B1") (pintype "bidirectional"))
    )
    (net (code "41") (name "Net-(U1-B2-Pad16)") (class "Default")
      (node (ref "U1") (pin "16") (pinfunction "B2_16") (pintype "bidirectional"))
      (node (ref "U1") (pin "52") (pinfunction "B2_52") (pintype "bidirectional"))
      (node (ref "U1") (pin "B2") (pinfunction "B2_B2") (pintype "bidirectional"))
    )
    (net (code "42") (name "Net-(U1-B3-Pad15)") (class "Default")
      (node (ref "U1") (pin "15") (pinfunction "B3_15") (pintype "bidirectional"))
      (node (ref "U1") (pin "51") (pinfunction "B3_51") (pintype "bidirectional"))
      (node (ref "U1") (pin "B3") (pinfunction "B3_B3") (pintype "bidirectional"))
    )
    (net (code "43") (name "Net-(U1-B4-Pad14)") (class "Default")
      (node (ref "U1") (pin "14") (pinfunction "B4_14") (pintype "bidirectional"))
      (node (ref "U1") (pin "50") (pinfunction "B4_50") (pintype "bidirectional"))
      (node (ref "U1") (pin "B4") (pinfunction "B4_B4") (pintype "bidirectional"))
    )
    (net (code "44") (name "Net-(U1-B5-Pad13)") (class "Default")
      (node (ref "U1") (pin "13") (pinfunction "B5_13") (pintype "bidirectional"))
      (node (ref "U1") (pin "49") (pinfunction "B5_49") (pintype "bidirectional"))
      (node (ref "U1") (pin "B5") (pinfunction "B5_B5") (pintype "bidirectional"))
    )
    (net (code "45") (name "Net-(U1-C0-Pad108)") (class "Default")
      (node (ref "U1") (pin "108") (pinfunction "C0_108") (pintype "bidirectional"))
      (node (ref "U1") (pin "72") (pinfunction "C0_72") (pintype "bidirectional"))
      (node (ref "U1") (pin "C0") (pinfunction "C0_C0") (pintype "bidirectional"))
    )
    (net (code "46") (name "Net-(U1-C1-Pad107)") (class "Default")
      (node (ref "U1") (pin "107") (pinfunction "C1_107") (pintype "bidirectional"))
      (node (ref "U1") (pin "71") (pinfunction "C1_71") (pintype "bidirectional"))
      (node (ref "U1") (pin "C1") (pinfunction "C1_C1") (pintype "bidirectional"))
    )
    (net (code "47") (name "Net-(U1-C2-Pad106)") (class "Default")
      (node (ref "U1") (pin "106") (pinfunction "C2_106") (pintype "bidirectional"))
      (node (ref "U1") (pin "70") (pinfunction "C2_70") (pintype "bidirectional"))
      (node (ref "U1") (pin "C2") (pinfunction "C2_C2") (pintype "bidirectional"))
    )
    (net (code "48") (name "Net-(U1-C3-Pad105)") (class "Default")
      (node (ref "U1") (pin "105") (pinfunction "C3_105") (pintype "bidirectional"))
      (node (ref "U1") (pin "69") (pinfunction "C3_69") (pintype "bidirectional"))
      (node (ref "U1") (pin "C3") (pinfunction "C3_C3") (pintype "bidirectional"))
    )
    (net (code "49") (name "Net-(U1-C4-Pad104)") (class "Default")
      (node (ref "U1") (pin "104") (pinfunction "C4_104") (pintype "bidirectional"))
      (node (ref "U1") (pin "68") (pinfunction "C4_68") (pintype "bidirectional"))
      (node (ref "U1") (pin "C4") (pinfunction "C4_C4") (pintype "bidirectional"))
    )
    (net (code "50") (name "Net-(U1-C5-Pad103)") (class "Default")
      (node (ref "U1") (pin "103") (pinfunction "C5_103") (pintype "bidirectional"))
      (node (ref "U1") (pin "67") (pinfunction "C5_67") (pintype "bidirectional"))
      (node (ref "U1") (pin "C5") (pinfunction "C5_C5") (pintype "bidirectional"))
    )
    (net (code "51") (name "Net-(U1-D7-Pad59)") (class "Default")
      (node (ref "U1") (pin "59") (pinfunction "D7_59") (pintype "bidirectional"))
      (node (ref "U1") (pin "95") (pinfunction "D7_95") (pintype "bidirectional"))
      (node (ref "U1") (pin "D7") (pinfunction "D7_D7") (pintype "bidirectional"))
    )
    (net (code "52") (name "Net-(U1-PadRST)") (class "Default")
      (node (ref "U1") (pin "56") (pinfunction "RST_56") (pintype "bidirectional"))
      (node (ref "U1") (pin "92") (pinfunction "RST_92") (pintype "bidirectional"))
      (node (ref "U1") (pin "RST") (pinfunction "RST_RST") (pintype "bidirectional"))
    )
    (net (code "53") (name "Net-(U2-OUT)") (class "Default")
      (node (ref "U2") (pin "3") (pinfunction "OUT_3") (pintype "bidirectional"))
      (node (ref "U5") (pin "6") (pinfunction "MCLK_6") (pintype "bidirectional"))
    )
    (net (code "54") (name "Net-(U3-PROG)") (class "Default")
      (node (ref "R11") (pin "2") (pinfunction "2_2") (pintype "passive"))
      (node (ref "U3") (pin "5") (pinfunction "PROG_5") (pintype "input"))
    )
    (net (code "55") (name "Net-(U3-VBAT)") (class "Default")
      (node (ref "D2") (pin "A") (pinfunction "A_A") (pintype "passive"))
      (node (ref "JP19") (pin "1") (pinfunction "1_1") (pintype "passive"))
      (node (ref "U3") (pin "3") (pinfunction "VBAT_3") (pintype "power_in"))
    )
    (net (code "56") (name "SPI_BAR_SS") (class "Default")
      (node (ref "Q1") (pin "1") (pinfunction "G_1") (pintype "passive"))
      (node (ref "R4") (pin "1") (pinfunction "1_1") (pintype "passive"))
      (node (ref "U1") (pin "12") (pinfunction "A0_12") (pintype "bidirectional"))
      (node (ref "U1") (pin "48") (pinfunction "A0_48") (pintype "bidirectional"))
      (node (ref "U1") (pin "A0") (pinfunction "A0_A0") (pintype "bidirectional"))
    )
    (net (code "57") (name "SPI_FREE_SS") (class "Default")
      (node (ref "JP9") (pin "2") (pinfunction "2_2") (pintype "passive"))
      (node (ref "R2") (pin "1") (pinfunction "1_1") (pintype "passive"))
      (node (ref "U1") (pin "60") (pinfunction "D6_60") (pintype "bidirectional"))
      (node (ref "U1") (pin "96") (pinfunction "D6_96") (pintype "bidirectional"))
      (node (ref "U1") (pin "D6") (pinfunction "D6_D6") (pintype "bidirectional"))
    )
    (net (code "58") (name "SPI_MISO") (class "Default")
      (node (ref "JP9") (pin "3") (pinfunction "3_3") (pintype "passive"))
      (node (ref "U1") (pin "44") (pinfunction "A4_44") (pintype "bidirectional"))
      (node (ref "U1") (pin "8") (pinfunction "A4_8") (pintype "bidirectional"))
      (node (ref "U1") (pin "A4") (pinfunction "A4_A4") (pintype "bidirectional"))
      (node (ref "U5") (pin "8") (pinfunction "DOUT_8") (pintype "bidirectional"))
      (node (ref "U6") (pin "7") (pinfunction "DATA_OUT_7") (pintype "output"))
    )
    (net (code "59") (name "SPI_MOSI") (class "Default")
      (node (ref "JP9") (pin "4") (pinfunction "4_4") (pintype "passive"))
      (node (ref "U1") (pin "43") (pinfunction "A5_43") (pintype "bidirectional"))
      (node (ref "U1") (pin "7") (pinfunction "A5_7") (pintype "bidirectional"))
      (node (ref "U1") (pin "A5") (pinfunction "A5_A5") (pintype "bidirectional"))
      (node (ref "U5") (pin "7") (pinfunction "DIN_7") (pintype "bidirectional"))
      (node (ref "U6") (pin "3") (pinfunction "DATA_IN_3") (pintype "input"))
    )
    (net (code "60") (name "SPI_SCK") (class "Default")
      (node (ref "JP9") (pin "5") (pinfunction "5_5") (pintype "passive"))
      (node (ref "U1") (pin "45") (pinfunction "A3_45") (pintype "bidirectional"))
      (node (ref "U1") (pin "9") (pinfunction "A3_9") (pintype "bidirectional"))
      (node (ref "U1") (pin "A3") (pinfunction "A3_A3") (pintype "bidirectional"))
      (node (ref "U5") (pin "1") (pinfunction "SCLK_1") (pintype "bidirectional"))
      (node (ref "U6") (pin "5") (pinfunction "SCLK_5") (pintype "input"))
    )
    (net (code "61") (name "SPI_SDC_SS") (class "Default")
      (node (ref "R3") (pin "1") (pinfunction "1_1") (pintype "passive"))
      (node (ref "U1") (pin "10") (pinfunction "A2_10") (pintype "bidirectional"))
      (node (ref "U1") (pin "46") (pinfunction "A2_46") (pintype "bidirectional"))
      (node (ref "U1") (pin "A2") (pinfunction "A2_A2") (pintype "bidirectional"))
      (node (ref "U6") (pin "2") (pinfunction "CS_2") (pintype "input"))
    )
    (net (code "62") (name "VOC_AIN") (class "Default")
      (node (ref "JP13") (pin "7") (pinfunction "7_7") (pintype "passive"))
      (node (ref "JP14") (pin "1") (pinfunction "1_1") (pintype "passive"))
      (node (ref "U9") (pin "7") (pinfunction "AIN3_7") (pintype "input"))
    )
    (net (code "63") (name "WKP") (class "Default")
      (node (ref "JP18") (pin "2") (pinfunction "2_2") (pintype "passive"))
      (node (ref "U1") (pin "41") (pinfunction "WKP_41") (pintype "bidirectional"))
      (node (ref "U1") (pin "5") (pinfunction "WKP_5") (pintype "bidirectional"))
      (node (ref "U1") (pin "WKP") (pinfunction "WKP_WKP") (pintype "bidirectional"))
    )
    (net (code "64") (name "unconnected-(IC1-NC-Pad3)") (class "Default")
      (node (ref "IC1") (pin "3") (pinfunction "NC_3") (pintype "input"))
    )
    (net (code "65") (name "unconnected-(U4-NC-PadP6)") (class "Default")
      (node (ref "U4") (pin "P6") (pinfunction "NC_P6") (pintype "no_connect"))
    )
    (net (code "66") (name "unconnected-(U5-NC(PEN)-Pad4)") (class "Default")
      (node (ref "U5") (pin "4") (pinfunction "NC(PEN)_4") (pintype "bidirectional"))
    )
    (net (code "67") (name "unconnected-(U5-NC(PV)-Pad3)") (class "Default")
      (node (ref "U5") (pin "3") (pinfunction "NC(PV)_3") (pintype "bidirectional"))
    )
    (net (code "68") (name "unconnected-(U6-CARD_DETECT-PadCD1)") (class "Default")
      (node (ref "U6") (pin "CD1") (pinfunction "CARD_DETECT_CD1") (pintype "passive"))
    )
    (net (code "69") (name "unconnected-(U6-CARD_DETECT1-PadCD2)") (class "Default")
      (node (ref "U6") (pin "CD2") (pinfunction "CARD_DETECT1_CD2") (pintype "passive"))
    )
    (net (code "70") (name "unconnected-(U6-DAT1-Pad8)") (class "Default")
      (node (ref "U6") (pin "8") (pinfunction "DAT1_8") (pintype "bidirectional"))
    )
    (net (code "71") (name "unconnected-(U6-DAT2-Pad1)") (class "Default")
      (node (ref "U6") (pin "1") (pinfunction "DAT2_1") (pintype "bidirectional"))
    )
    (net (code "72") (name "unconnected-(U7-PadNC1)") (class "Default")
      (node (ref "U7") (pin "NC1") (pinfunction "NC1_NC1") (pintype "bidirectional"))
    )
    (net (code "73") (name "unconnected-(U7-PadNC2)") (class "Default")
      (node (ref "U7") (pin "NC2") (pinfunction "NC2_NC2") (pintype "bidirectional"))
    )
    (net (code "74") (name "unconnected-(U7-PadNC3)") (class "Default")
      (node (ref "U7") (pin "NC3") (pinfunction "NC3_NC3") (pintype "bidirectional"))
    )
    (net (code "75") (name "unconnected-(U7-PadNV1)") (class "Default")
      (node (ref "U7") (pin "NV1") (pinfunction "NV1_NV1") (pintype "bidirectional"))
    )
    (net (code "76") (name "unconnected-(U7-PadNV2)") (class "Default")
      (node (ref "U7") (pin "NV2") (pinfunction "NV2_NV2") (pintype "bidirectional"))
    )
    (net (code "77") (name "unconnected-(U7-PadRESETB)") (class "Default")
      (node (ref "U7") (pin "RESETB") (pinfunction "RESETB_RESETB") (pintype "bidirectional"))
    )
    (net (code "78") (name "unconnected-(U7-PadUART_CTS)") (class "Default")
      (node (ref "U7") (pin "UART_CTS") (pinfunction "UART_CTS_UART_CTS") (pintype "bidirectional"))
    )
    (net (code "79") (name "unconnected-(U7-PadUART_RTS)") (class "Default")
      (node (ref "U7") (pin "UART_RTS") (pinfunction "UART_RTS_UART_RTS") (pintype "bidirectional"))
    )
  )
)
